# MKR-I2C-shield.net
KiCad netlist of a schematic drawn in EAGLE
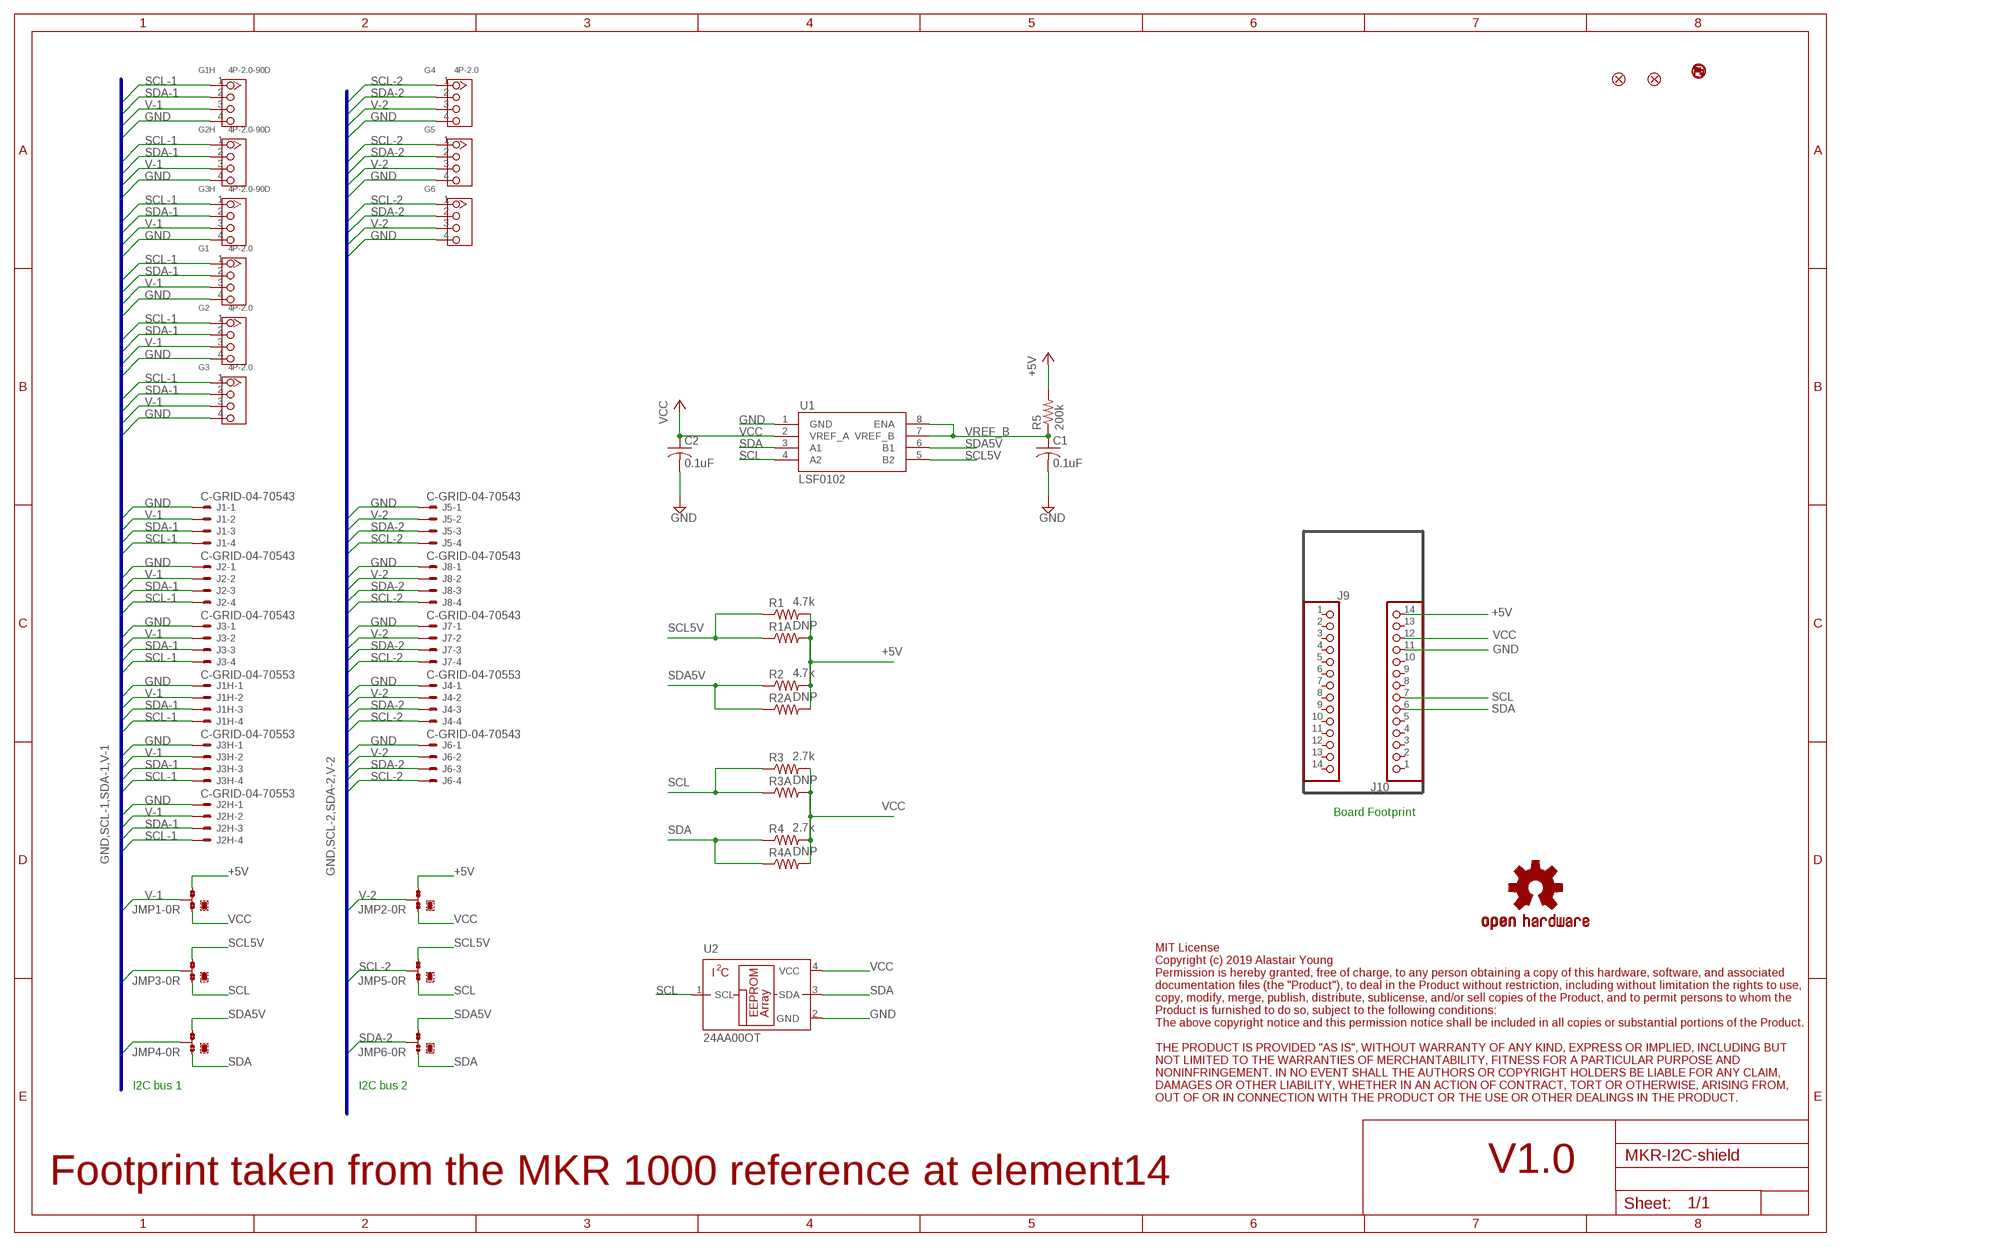
[diagram p0: schematic, sheet 1]

(export (version "E")
  (design (tool "Eeschema 10.0.6"))
  (components
    (comp (ref "C1")
      (value "0.1uF")
      (footprint "eagle-import:C0603")
      (libsource (lib "eagle-import") (part "C-USC0603"))
    )
    (comp (ref "C2")
      (value "0.1uF")
      (footprint "eagle-import:C0603")
      (libsource (lib "eagle-import") (part "C-USC0603"))
    )
    (comp (ref "FD1")
      (value "FIDUCIAL1X2")
      (footprint "eagle-import:FIDUCIAL-1X2")
      (libsource (lib "eagle-import") (part "FIDUCIAL1X2"))
    )
    (comp (ref "FD2")
      (value "FIDUCIAL1X2")
      (footprint "eagle-import:FIDUCIAL-1X2")
      (libsource (lib "eagle-import") (part "FIDUCIAL1X2"))
    )
    (comp (ref "G1")
      (value "4P-2.0")
      (footprint "eagle-import:HW4-2.0")
      (libsource (lib "eagle-import") (part "GROVE-CONNECTOR-DIP(4P-2.0)"))
    )
    (comp (ref "G1H")
      (value "4P-2.0-90D")
      (footprint "eagle-import:HW4-2.0-90D")
      (libsource (lib "eagle-import") (part "GROVE-CONNECTOR-DIP-90D(4P-2.0)"))
    )
    (comp (ref "G2")
      (value "4P-2.0")
      (footprint "eagle-import:HW4-2.0")
      (libsource (lib "eagle-import") (part "GROVE-CONNECTOR-DIP(4P-2.0)"))
    )
    (comp (ref "G2H")
      (value "4P-2.0-90D")
      (footprint "eagle-import:HW4-2.0-90D")
      (libsource (lib "eagle-import") (part "GROVE-CONNECTOR-DIP-90D(4P-2.0)"))
    )
    (comp (ref "G3")
      (value "4P-2.0")
      (footprint "eagle-import:HW4-2.0")
      (libsource (lib "eagle-import") (part "GROVE-CONNECTOR-DIP(4P-2.0)"))
    )
    (comp (ref "G3H")
      (value "4P-2.0-90D")
      (footprint "eagle-import:HW4-2.0-90D")
      (libsource (lib "eagle-import") (part "GROVE-CONNECTOR-DIP-90D(4P-2.0)"))
    )
    (comp (ref "G4")
      (value "4P-2.0")
      (footprint "eagle-import:HW4-2.0")
      (libsource (lib "eagle-import") (part "GROVE-CONNECTOR-DIP(4P-2.0)"))
    )
    (comp (ref "G5")
      (value "4P-2.0")
      (footprint "eagle-import:HW4-2.0")
      (libsource (lib "eagle-import") (part "GROVE-CONNECTOR-DIP(4P-2.0)"))
    )
    (comp (ref "G6")
      (value "4P-2.0")
      (footprint "eagle-import:HW4-2.0")
      (libsource (lib "eagle-import") (part "GROVE-CONNECTOR-DIP(4P-2.0)"))
    )
    (comp (ref "J1")
      (value "C-GRID-04-70543")
      (footprint "eagle-import:70543-04")
      (fields (field (name "MF") "MOLEX"))
      (libsource (lib "eagle-import") (part "C-GRID-04-70543"))
    )
    (comp (ref "J1H")
      (value "C-GRID-04-70553")
      (footprint "eagle-import:70553-04")
      (fields (field (name "MF") "MOLEX"))
      (libsource (lib "eagle-import") (part "C-GRID-04-70553"))
    )
    (comp (ref "J2")
      (value "C-GRID-04-70543")
      (footprint "eagle-import:70543-04")
      (fields (field (name "MF") "MOLEX"))
      (libsource (lib "eagle-import") (part "C-GRID-04-70543"))
    )
    (comp (ref "J2H")
      (value "C-GRID-04-70553")
      (footprint "eagle-import:70553-04")
      (fields (field (name "MF") "MOLEX"))
      (libsource (lib "eagle-import") (part "C-GRID-04-70553"))
    )
    (comp (ref "J3")
      (value "C-GRID-04-70543")
      (footprint "eagle-import:70543-04")
      (fields (field (name "MF") "MOLEX"))
      (libsource (lib "eagle-import") (part "C-GRID-04-70543"))
    )
    (comp (ref "J3H")
      (value "C-GRID-04-70553")
      (footprint "eagle-import:70553-04")
      (fields (field (name "MF") "MOLEX"))
      (libsource (lib "eagle-import") (part "C-GRID-04-70553"))
    )
    (comp (ref "J4")
      (value "C-GRID-04-70553")
      (footprint "eagle-import:70553-04")
      (fields (field (name "MF") "MOLEX"))
      (libsource (lib "eagle-import") (part "C-GRID-04-70553"))
    )
    (comp (ref "J5")
      (value "C-GRID-04-70543")
      (footprint "eagle-import:70543-04")
      (fields (field (name "MF") "MOLEX"))
      (libsource (lib "eagle-import") (part "C-GRID-04-70543"))
    )
    (comp (ref "J6")
      (value "C-GRID-04-70543")
      (footprint "eagle-import:70543-04")
      (fields (field (name "MF") "MOLEX"))
      (libsource (lib "eagle-import") (part "C-GRID-04-70543"))
    )
    (comp (ref "J7")
      (value "C-GRID-04-70543")
      (footprint "eagle-import:70543-04")
      (fields (field (name "MF") "MOLEX"))
      (libsource (lib "eagle-import") (part "C-GRID-04-70543"))
    )
    (comp (ref "J8")
      (value "C-GRID-04-70543")
      (footprint "eagle-import:70543-04")
      (fields (field (name "MF") "MOLEX"))
      (libsource (lib "eagle-import") (part "C-GRID-04-70543"))
    )
    (comp (ref "J9")
      (value "DNP")
      (footprint "eagle-import:1X14")
      (libsource (lib "eagle-import") (part "PINHD-1X14"))
    )
    (comp (ref "J10")
      (value "DNP")
      (footprint "eagle-import:1X14")
      (libsource (lib "eagle-import") (part "PINHD-1X14"))
    )
    (comp (ref "JMP1")
      (value "0R-JUMPB")
      (footprint "eagle-import:B0R-JMP")
      (libsource (lib "eagle-import") (part "0R-JUMPB"))
    )
    (comp (ref "JMP2")
      (value "0R-JUMPB")
      (footprint "eagle-import:B0R-JMP")
      (libsource (lib "eagle-import") (part "0R-JUMPB"))
    )
    (comp (ref "JMP3")
      (value "0R-JUMPB")
      (footprint "eagle-import:B0R-JMP")
      (libsource (lib "eagle-import") (part "0R-JUMPB"))
    )
    (comp (ref "JMP4")
      (value "0R-JUMPB")
      (footprint "eagle-import:B0R-JMP")
      (libsource (lib "eagle-import") (part "0R-JUMPB"))
    )
    (comp (ref "JMP5")
      (value "0R-JUMPB")
      (footprint "eagle-import:B0R-JMP")
      (libsource (lib "eagle-import") (part "0R-JUMPB"))
    )
    (comp (ref "JMP6")
      (value "0R-JUMPB")
      (footprint "eagle-import:B0R-JMP")
      (libsource (lib "eagle-import") (part "0R-JUMPB"))
    )
    (comp (ref "LOGO1")
      (value "OSHW-LOGOL")
      (footprint "eagle-import:OSHW-LOGO-L")
      (libsource (lib "eagle-import") (part "OSHW-LOGOL"))
    )
    (comp (ref "LOGO2")
      (value "NO_PB_LOGO")
      (footprint "eagle-import:NO_PB_LOGO_0.120")
      (libsource (lib "eagle-import") (part "NO_PB_LOGO"))
    )
    (comp (ref "R1")
      (value "4.7k")
      (footprint "eagle-import:R0603")
      (libsource (lib "eagle-import") (part "R-US_R0603"))
    )
    (comp (ref "R1A")
      (value "DNP")
      (footprint "eagle-import:0204_5")
      (libsource (lib "eagle-import") (part "R-US_0204/5"))
    )
    (comp (ref "R2")
      (value "4.7k")
      (footprint "eagle-import:R0603")
      (libsource (lib "eagle-import") (part "R-US_R0603"))
    )
    (comp (ref "R2A")
      (value "DNP")
      (footprint "eagle-import:0204_5")
      (libsource (lib "eagle-import") (part "R-US_0204/5"))
    )
    (comp (ref "R3")
      (value "2.7k")
      (footprint "eagle-import:R0603")
      (libsource (lib "eagle-import") (part "R-US_R0603"))
    )
    (comp (ref "R3A")
      (value "DNP")
      (footprint "eagle-import:0204_5")
      (libsource (lib "eagle-import") (part "R-US_0204/5"))
    )
    (comp (ref "R4")
      (value "2.7k")
      (footprint "eagle-import:R0603")
      (libsource (lib "eagle-import") (part "R-US_R0603"))
    )
    (comp (ref "R4A")
      (value "DNP")
      (footprint "eagle-import:0204_5")
      (libsource (lib "eagle-import") (part "R-US_0204/5"))
    )
    (comp (ref "R5")
      (value "200k")
      (footprint "eagle-import:R0603")
      (libsource (lib "eagle-import") (part "R-US_R0603"))
    )
    (comp (ref "U1")
      (value "LSF0102")
      (footprint "eagle-import:DCT_R-PDSO-G8")
      (libsource (lib "eagle-import") (part "LSF0102"))
    )
    (comp (ref "U2")
      (value "24AA00OT")
      (footprint "eagle-import:SOT23-5L")
      (fields (field (name "MF") "MICROCHIP") (field (name "MPN") "24AA00T-I/OTG"))
      (libsource (lib "eagle-import") (part "2400OTAA"))
    )
  )
  (nets
    (net (code "1") (name "+5V") (class "Default")
      (node (ref "J10") (pin "14") (pinfunction "14_14") (pintype "passive"))
      (node (ref "JMP1") (pin "3") (pinfunction "3_3") (pintype "passive"))
      (node (ref "JMP2") (pin "3") (pinfunction "3_3") (pintype "passive"))
      (node (ref "R1") (pin "2") (pinfunction "2_2") (pintype "passive"))
      (node (ref "R1A") (pin "2") (pinfunction "2_2") (pintype "passive"))
      (node (ref "R2") (pin "2") (pinfunction "2_2") (pintype "passive"))
      (node (ref "R2A") (pin "2") (pinfunction "2_2") (pintype "passive"))
      (node (ref "R5") (pin "2") (pinfunction "2_2") (pintype "passive"))
    )
    (net (code "2") (name "/SCL") (class "Default")
      (node (ref "J10") (pin "7") (pinfunction "7_7") (pintype "passive"))
      (node (ref "JMP3") (pin "1") (pinfunction "1_1") (pintype "passive"))
      (node (ref "JMP5") (pin "1") (pinfunction "1_1") (pintype "passive"))
      (node (ref "R3") (pin "1") (pinfunction "1_1") (pintype "passive"))
      (node (ref "R3A") (pin "1") (pinfunction "1_1") (pintype "passive"))
      (node (ref "U1") (pin "4") (pinfunction "A2_4") (pintype "bidirectional"))
      (node (ref "U2") (pin "1") (pinfunction "SCL_1") (pintype "input"))
    )
    (net (code "3") (name "/SCL-1") (class "Default")
      (node (ref "G1") (pin "1") (pinfunction "1_1") (pintype "bidirectional"))
      (node (ref "G1H") (pin "1") (pinfunction "1_1") (pintype "bidirectional"))
      (node (ref "G2") (pin "1") (pinfunction "1_1") (pintype "bidirectional"))
      (node (ref "G2H") (pin "1") (pinfunction "1_1") (pintype "bidirectional"))
      (node (ref "G3") (pin "1") (pinfunction "1_1") (pintype "bidirectional"))
      (node (ref "G3H") (pin "1") (pinfunction "1_1") (pintype "bidirectional"))
      (node (ref "J1") (pin "4") (pinfunction "S_4") (pintype "passive"))
      (node (ref "J1H") (pin "4") (pinfunction "S_4") (pintype "passive"))
      (node (ref "J2") (pin "4") (pinfunction "S_4") (pintype "passive"))
      (node (ref "J2H") (pin "4") (pinfunction "S_4") (pintype "passive"))
      (node (ref "J3") (pin "4") (pinfunction "S_4") (pintype "passive"))
      (node (ref "J3H") (pin "4") (pinfunction "S_4") (pintype "passive"))
      (node (ref "JMP3") (pin "2") (pinfunction "2_2") (pintype "passive"))
    )
    (net (code "4") (name "/SCL-2") (class "Default")
      (node (ref "G4") (pin "1") (pinfunction "1_1") (pintype "bidirectional"))
      (node (ref "G5") (pin "1") (pinfunction "1_1") (pintype "bidirectional"))
      (node (ref "G6") (pin "1") (pinfunction "1_1") (pintype "bidirectional"))
      (node (ref "J4") (pin "4") (pinfunction "S_4") (pintype "passive"))
      (node (ref "J5") (pin "4") (pinfunction "S_4") (pintype "passive"))
      (node (ref "J6") (pin "4") (pinfunction "S_4") (pintype "passive"))
      (node (ref "J7") (pin "4") (pinfunction "S_4") (pintype "passive"))
      (node (ref "J8") (pin "4") (pinfunction "S_4") (pintype "passive"))
      (node (ref "JMP5") (pin "2") (pinfunction "2_2") (pintype "passive"))
    )
    (net (code "5") (name "/SCL5V") (class "Default")
      (node (ref "JMP3") (pin "3") (pinfunction "3_3") (pintype "passive"))
      (node (ref "JMP5") (pin "3") (pinfunction "3_3") (pintype "passive"))
      (node (ref "R1") (pin "1") (pinfunction "1_1") (pintype "passive"))
      (node (ref "R1A") (pin "1") (pinfunction "1_1") (pintype "passive"))
      (node (ref "U1") (pin "5") (pinfunction "B2_5") (pintype "bidirectional"))
    )
    (net (code "6") (name "/SDA") (class "Default")
      (node (ref "J10") (pin "6") (pinfunction "6_6") (pintype "passive"))
      (node (ref "JMP4") (pin "1") (pinfunction "1_1") (pintype "passive"))
      (node (ref "JMP6") (pin "1") (pinfunction "1_1") (pintype "passive"))
      (node (ref "R4") (pin "1") (pinfunction "1_1") (pintype "passive"))
      (node (ref "R4A") (pin "1") (pinfunction "1_1") (pintype "passive"))
      (node (ref "U1") (pin "3") (pinfunction "A1_3") (pintype "bidirectional"))
      (node (ref "U2") (pin "3") (pinfunction "SDA_3") (pintype "bidirectional"))
    )
    (net (code "7") (name "/SDA-1") (class "Default")
      (node (ref "G1") (pin "2") (pinfunction "2_2") (pintype "bidirectional"))
      (node (ref "G1H") (pin "2") (pinfunction "2_2") (pintype "bidirectional"))
      (node (ref "G2") (pin "2") (pinfunction "2_2") (pintype "bidirectional"))
      (node (ref "G2H") (pin "2") (pinfunction "2_2") (pintype "bidirectional"))
      (node (ref "G3") (pin "2") (pinfunction "2_2") (pintype "bidirectional"))
      (node (ref "G3H") (pin "2") (pinfunction "2_2") (pintype "bidirectional"))
      (node (ref "J1") (pin "3") (pinfunction "S_3") (pintype "passive"))
      (node (ref "J1H") (pin "3") (pinfunction "S_3") (pintype "passive"))
      (node (ref "J2") (pin "3") (pinfunction "S_3") (pintype "passive"))
      (node (ref "J2H") (pin "3") (pinfunction "S_3") (pintype "passive"))
      (node (ref "J3") (pin "3") (pinfunction "S_3") (pintype "passive"))
      (node (ref "J3H") (pin "3") (pinfunction "S_3") (pintype "passive"))
      (node (ref "JMP4") (pin "2") (pinfunction "2_2") (pintype "passive"))
    )
    (net (code "8") (name "/SDA-2") (class "Default")
      (node (ref "G4") (pin "2") (pinfunction "2_2") (pintype "bidirectional"))
      (node (ref "G5") (pin "2") (pinfunction "2_2") (pintype "bidirectional"))
      (node (ref "G6") (pin "2") (pinfunction "2_2") (pintype "bidirectional"))
      (node (ref "J4") (pin "3") (pinfunction "S_3") (pintype "passive"))
      (node (ref "J5") (pin "3") (pinfunction "S_3") (pintype "passive"))
      (node (ref "J6") (pin "3") (pinfunction "S_3") (pintype "passive"))
      (node (ref "J7") (pin "3") (pinfunction "S_3") (pintype "passive"))
      (node (ref "J8") (pin "3") (pinfunction "S_3") (pintype "passive"))
      (node (ref "JMP6") (pin "2") (pinfunction "2_2") (pintype "passive"))
    )
    (net (code "9") (name "/SDA5V") (class "Default")
      (node (ref "JMP4") (pin "3") (pinfunction "3_3") (pintype "passive"))
      (node (ref "JMP6") (pin "3") (pinfunction "3_3") (pintype "passive"))
      (node (ref "R2") (pin "1") (pinfunction "1_1") (pintype "passive"))
      (node (ref "R2A") (pin "1") (pinfunction "1_1") (pintype "passive"))
      (node (ref "U1") (pin "6") (pinfunction "B1_6") (pintype "bidirectional"))
    )
    (net (code "10") (name "/V-1") (class "Default")
      (node (ref "G1") (pin "3") (pinfunction "3_3") (pintype "bidirectional"))
      (node (ref "G1H") (pin "3") (pinfunction "3_3") (pintype "bidirectional"))
      (node (ref "G2") (pin "3") (pinfunction "3_3") (pintype "bidirectional"))
      (node (ref "G2H") (pin "3") (pinfunction "3_3") (pintype "bidirectional"))
      (node (ref "G3") (pin "3") (pinfunction "3_3") (pintype "bidirectional"))
      (node (ref "G3H") (pin "3") (pinfunction "3_3") (pintype "bidirectional"))
      (node (ref "J1") (pin "2") (pinfunction "S_2") (pintype "passive"))
      (node (ref "J1H") (pin "2") (pinfunction "S_2") (pintype "passive"))
      (node (ref "J2") (pin "2") (pinfunction "S_2") (pintype "passive"))
      (node (ref "J2H") (pin "2") (pinfunction "S_2") (pintype "passive"))
      (node (ref "J3") (pin "2") (pinfunction "S_2") (pintype "passive"))
      (node (ref "J3H") (pin "2") (pinfunction "S_2") (pintype "passive"))
      (node (ref "JMP1") (pin "2") (pinfunction "2_2") (pintype "passive"))
    )
    (net (code "11") (name "/V-2") (class "Default")
      (node (ref "G4") (pin "3") (pinfunction "3_3") (pintype "bidirectional"))
      (node (ref "G5") (pin "3") (pinfunction "3_3") (pintype "bidirectional"))
      (node (ref "G6") (pin "3") (pinfunction "3_3") (pintype "bidirectional"))
      (node (ref "J4") (pin "2") (pinfunction "S_2") (pintype "passive"))
      (node (ref "J5") (pin "2") (pinfunction "S_2") (pintype "passive"))
      (node (ref "J6") (pin "2") (pinfunction "S_2") (pintype "passive"))
      (node (ref "J7") (pin "2") (pinfunction "S_2") (pintype "passive"))
      (node (ref "J8") (pin "2") (pinfunction "S_2") (pintype "passive"))
      (node (ref "JMP2") (pin "2") (pinfunction "2_2") (pintype "passive"))
    )
    (net (code "12") (name "/VREF_B") (class "Default")
      (node (ref "C1") (pin "1") (pinfunction "1_1") (pintype "passive"))
      (node (ref "R5") (pin "1") (pinfunction "1_1") (pintype "passive"))
      (node (ref "U1") (pin "7") (pinfunction "VREF_B_7") (pintype "power_in"))
      (node (ref "U1") (pin "8") (pinfunction "ENA_8") (pintype "input"))
    )
    (net (code "15") (name "GND") (class "Default")
      (node (ref "C1") (pin "2") (pinfunction "2_2") (pintype "passive"))
      (node (ref "C2") (pin "2") (pinfunction "2_2") (pintype "passive"))
      (node (ref "G1") (pin "4") (pinfunction "4_4") (pintype "bidirectional"))
      (node (ref "G1H") (pin "4") (pinfunction "4_4") (pintype "bidirectional"))
      (node (ref "G2") (pin "4") (pinfunction "4_4") (pintype "bidirectional"))
      (node (ref "G2H") (pin "4") (pinfunction "4_4") (pintype "bidirectional"))
      (node (ref "G3") (pin "4") (pinfunction "4_4") (pintype "bidirectional"))
      (node (ref "G3H") (pin "4") (pinfunction "4_4") (pintype "bidirectional"))
      (node (ref "G4") (pin "4") (pinfunction "4_4") (pintype "bidirectional"))
      (node (ref "G5") (pin "4") (pinfunction "4_4") (pintype "bidirectional"))
      (node (ref "G6") (pin "4") (pinfunction "4_4") (pintype "bidirectional"))
      (node (ref "J1") (pin "1") (pinfunction "S_1") (pintype "passive"))
      (node (ref "J10") (pin "11") (pinfunction "11_11") (pintype "passive"))
      (node (ref "J1H") (pin "1") (pinfunction "S_1") (pintype "passive"))
      (node (ref "J2") (pin "1") (pinfunction "S_1") (pintype "passive"))
      (node (ref "J2H") (pin "1") (pinfunction "S_1") (pintype "passive"))
      (node (ref "J3") (pin "1") (pinfunction "S_1") (pintype "passive"))
      (node (ref "J3H") (pin "1") (pinfunction "S_1") (pintype "passive"))
      (node (ref "J4") (pin "1") (pinfunction "S_1") (pintype "passive"))
      (node (ref "J5") (pin "1") (pinfunction "S_1") (pintype "passive"))
      (node (ref "J6") (pin "1") (pinfunction "S_1") (pintype "passive"))
      (node (ref "J7") (pin "1") (pinfunction "S_1") (pintype "passive"))
      (node (ref "J8") (pin "1") (pinfunction "S_1") (pintype "passive"))
      (node (ref "U1") (pin "1") (pinfunction "GND_1") (pintype "power_in"))
      (node (ref "U2") (pin "2") (pinfunction "GND_2") (pintype "power_in"))
    )
    (net (code "16") (name "VCC") (class "Default")
      (node (ref "C2") (pin "1") (pinfunction "1_1") (pintype "passive"))
      (node (ref "J10") (pin "12") (pinfunction "12_12") (pintype "passive"))
      (node (ref "JMP1") (pin "1") (pinfunction "1_1") (pintype "passive"))
      (node (ref "JMP2") (pin "1") (pinfunction "1_1") (pintype "passive"))
      (node (ref "R3") (pin "2") (pinfunction "2_2") (pintype "passive"))
      (node (ref "R3A") (pin "2") (pinfunction "2_2") (pintype "passive"))
      (node (ref "R4") (pin "2") (pinfunction "2_2") (pintype "passive"))
      (node (ref "R4A") (pin "2") (pinfunction "2_2") (pintype "passive"))
      (node (ref "U1") (pin "2") (pinfunction "VREF_A_2") (pintype "power_in"))
      (node (ref "U2") (pin "4") (pinfunction "VCC_4") (pintype "power_in"))
    )
    (net (code "17") (name "unconnected-(J9-Pad1)") (class "Default")
      (node (ref "J9") (pin "1") (pinfunction "1_1") (pintype "passive"))
    )
    (net (code "18") (name "unconnected-(J9-Pad2)") (class "Default")
      (node (ref "J9") (pin "2") (pinfunction "2_2") (pintype "passive"))
    )
    (net (code "19") (name "unconnected-(J9-Pad3)") (class "Default")
      (node (ref "J9") (pin "3") (pinfunction "3_3") (pintype "passive"))
    )
    (net (code "20") (name "unconnected-(J9-Pad4)") (class "Default")
      (node (ref "J9") (pin "4") (pinfunction "4_4") (pintype "passive"))
    )
    (net (code "21") (name "unconnected-(J9-Pad5)") (class "Default")
      (node (ref "J9") (pin "5") (pinfunction "5_5") (pintype "passive"))
    )
    (net (code "22") (name "unconnected-(J9-Pad6)") (class "Default")
      (node (ref "J9") (pin "6") (pinfunction "6_6") (pintype "passive"))
    )
    (net (code "23") (name "unconnected-(J9-Pad7)") (class "Default")
      (node (ref "J9") (pin "7") (pinfunction "7_7") (pintype "passive"))
    )
    (net (code "24") (name "unconnected-(J9-Pad8)") (class "Default")
      (node (ref "J9") (pin "8") (pinfunction "8_8") (pintype "passive"))
    )
    (net (code "25") (name "unconnected-(J9-Pad9)") (class "Default")
      (node (ref "J9") (pin "9") (pinfunction "9_9") (pintype "passive"))
    )
    (net (code "26") (name "unconnected-(J9-Pad10)") (class "Default")
      (node (ref "J9") (pin "10") (pinfunction "10_10") (pintype "passive"))
    )
    (net (code "27") (name "unconnected-(J9-Pad11)") (class "Default")
      (node (ref "J9") (pin "11") (pinfunction "11_11") (pintype "passive"))
    )
    (net (code "28") (name "unconnected-(J9-Pad12)") (class "Default")
      (node (ref "J9") (pin "12") (pinfunction "12_12") (pintype "passive"))
    )
    (net (code "29") (name "unconnected-(J9-Pad13)") (class "Default")
      (node (ref "J9") (pin "13") (pinfunction "13_13") (pintype "passive"))
    )
    (net (code "30") (name "unconnected-(J9-Pad14)") (class "Default")
      (node (ref "J9") (pin "14") (pinfunction "14_14") (pintype "passive"))
    )
    (net (code "31") (name "unconnected-(J10-Pad1)") (class "Default")
      (node (ref "J10") (pin "1") (pinfunction "1_1") (pintype "passive"))
    )
    (net (code "32") (name "unconnected-(J10-Pad2)") (class "Default")
      (node (ref "J10") (pin "2") (pinfunction "2_2") (pintype "passive"))
    )
    (net (code "33") (name "unconnected-(J10-Pad3)") (class "Default")
      (node (ref "J10") (pin "3") (pinfunction "3_3") (pintype "passive"))
    )
    (net (code "34") (name "unconnected-(J10-Pad4)") (class "Default")
      (node (ref "J10") (pin "4") (pinfunction "4_4") (pintype "passive"))
    )
    (net (code "35") (name "unconnected-(J10-Pad5)") (class "Default")
      (node (ref "J10") (pin "5") (pinfunction "5_5") (pintype "passive"))
    )
    (net (code "36") (name "unconnected-(J10-Pad8)") (class "Default")
      (node (ref "J10") (pin "8") (pinfunction "8_8") (pintype "passive"))
    )
    (net (code "37") (name "unconnected-(J10-Pad9)") (class "Default")
      (node (ref "J10") (pin "9") (pinfunction "9_9") (pintype "passive"))
    )
    (net (code "38") (name "unconnected-(J10-Pad10)") (class "Default")
      (node (ref "J10") (pin "10") (pinfunction "10_10") (pintype "passive"))
    )
    (net (code "39") (name "unconnected-(J10-Pad13)") (class "Default")
      (node (ref "J10") (pin "13") (pinfunction "13_13") (pintype "passive"))
    )
  )
)
